# munia-snes.net
KiCad netlist of a schematic drawn in EAGLE
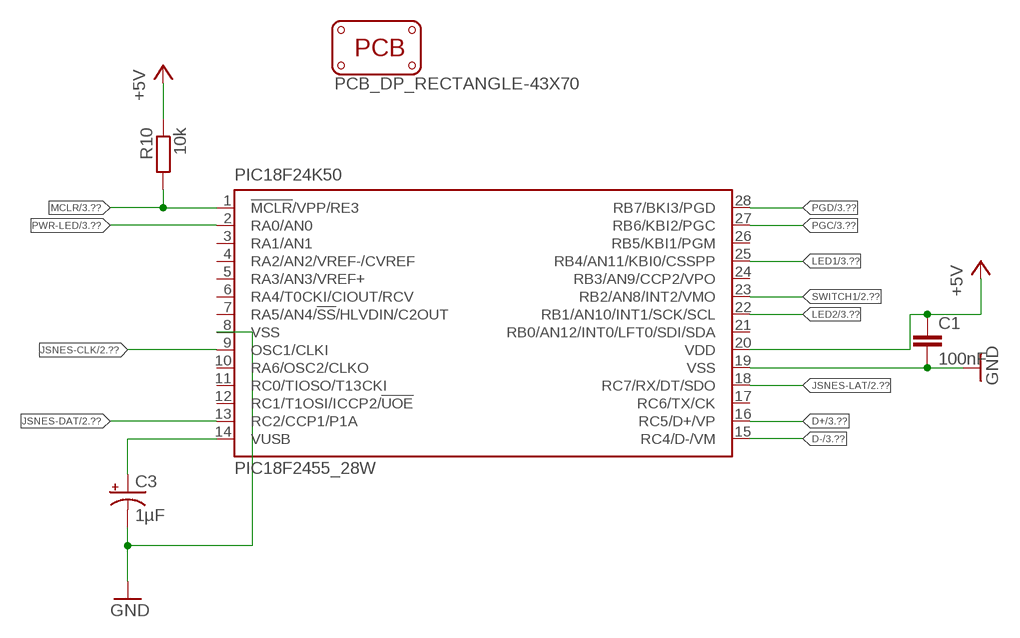
[diagram p0: schematic, sheet 1]
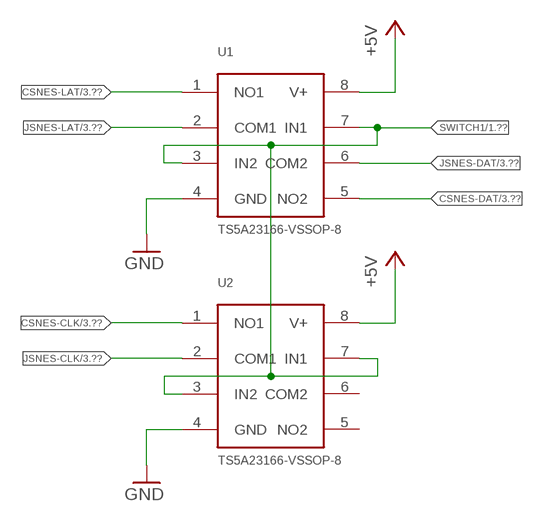
[diagram p1: schematic, sheet 2]
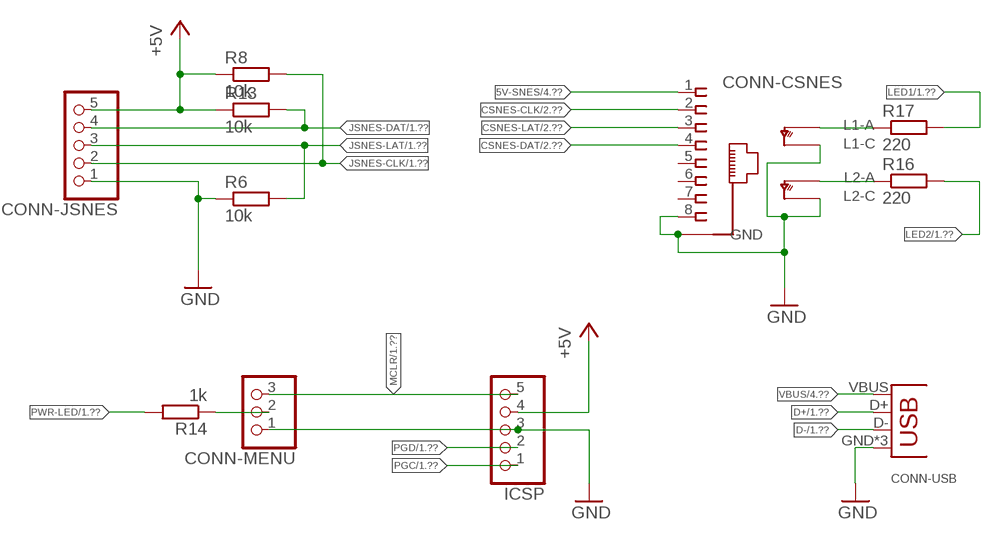
[diagram p2: schematic, sheet 3]
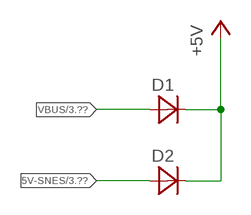
[diagram p3: schematic, sheet 4]

(export (version "E")
  (design (tool "Eeschema 10.0.6"))
  (components
    (comp (ref "C1")
      (value "100nF")
      (footprint "eagle-import:C0603")
      (libsource (lib "eagle-import") (part "C-EUC0603"))
    )
    (comp (ref "C3")
      (value "1µF")
      (footprint "eagle-import:EIA3216")
      (libsource (lib "eagle-import") (part "TANT-CAP1206"))
    )
    (comp (ref "PCB1")
      (value "PCB_DP_RECTANGLE-43X70")
      (footprint "eagle-import:DP7043_V1")
      (libsource (lib "eagle-import") (part "PCB_DP_RECTANGLE-43X70"))
    )
    (comp (ref "PIC18F24K50")
      (value "PIC18F2455_28W")
      (footprint "eagle-import:SO28W")
      (fields (field (name "MF") "MICROCHIP") (field (name "MPN") "PIC18F2455-I/SO"))
      (libsource (lib "eagle-import") (part "PIC18F2_28W455"))
    )
    (comp (ref "R10")
      (value "10k")
      (footprint "eagle-import:R0603")
      (libsource (lib "eagle-import") (part "R-EU_R0603"))
    )
    (comp (ref "U1")
      (value "TS5A23166-VSSOP-8")
      (footprint "eagle-import:SOT765")
      (libsource (lib "eagle-import") (part "TS5A23166-VSSOP-8"))
    )
    (comp (ref "U2")
      (value "TS5A23166-VSSOP-8")
      (footprint "eagle-import:SOT765")
      (libsource (lib "eagle-import") (part "TS5A23166-VSSOP-8"))
    )
    (comp (ref "CONN-CSNES")
      (value "RJ45-NIELS")
      (footprint "eagle-import:RJ45-NIELS")
      (libsource (lib "eagle-import") (part "RJ45-NIELS"))
    )
    (comp (ref "CONN-JSNES")
      (value "PINHD-1X5")
      (footprint "eagle-import:1X05")
      (libsource (lib "eagle-import") (part "PINHD-1X5"))
    )
    (comp (ref "CONN-MENU")
      (value "PINHD-1X3")
      (footprint "eagle-import:1X03")
      (libsource (lib "eagle-import") (part "PINHD-1X3"))
    )
    (comp (ref "CONN-USB")
      (value "USB-B-NIELS")
      (footprint "eagle-import:USB-B-H")
      (libsource (lib "eagle-import") (part "USB-B-NIELS"))
    )
    (comp (ref "ICSP")
      (value "PINHD-1X5")
      (footprint "eagle-import:1X05")
      (libsource (lib "eagle-import") (part "PINHD-1X5"))
    )
    (comp (ref "R6")
      (value "10k")
      (footprint "eagle-import:R0603")
      (libsource (lib "eagle-import") (part "R-EU_R0603"))
    )
    (comp (ref "R8")
      (value "10k")
      (footprint "eagle-import:R0603")
      (libsource (lib "eagle-import") (part "R-EU_R0603"))
    )
    (comp (ref "R13")
      (value "10k")
      (footprint "eagle-import:R0603")
      (libsource (lib "eagle-import") (part "R-EU_R0603"))
    )
    (comp (ref "R14")
      (value "1k")
      (footprint "eagle-import:R0603")
      (libsource (lib "eagle-import") (part "R-EU_R0603"))
    )
    (comp (ref "R16")
      (value "220")
      (footprint "eagle-import:R0603")
      (libsource (lib "eagle-import") (part "R-EU_R0603"))
    )
    (comp (ref "R17")
      (value "220")
      (footprint "eagle-import:R0603")
      (libsource (lib "eagle-import") (part "R-EU_R0603"))
    )
    (comp (ref "D1")
      (value "MBR120VLSFT1G")
      (footprint "eagle-import:SOD123")
      (libsource (lib "eagle-import") (part "MBR120VLSFT1G"))
    )
    (comp (ref "D2")
      (value "MBR120VLSFT1G")
      (footprint "eagle-import:SOD123")
      (libsource (lib "eagle-import") (part "MBR120VLSFT1G"))
    )
  )
  (nets
    (net (code "1") (name "+5V") (class "Default")
      (node (ref "C1") (pin "1") (pinfunction "1_1") (pintype "passive"))
      (node (ref "CONN-JSNES") (pin "5") (pinfunction "5_5") (pintype "passive"))
      (node (ref "D1") (pin "1") (pinfunction "C_1") (pintype "passive"))
      (node (ref "D2") (pin "1") (pinfunction "C_1") (pintype "passive"))
      (node (ref "ICSP") (pin "4") (pinfunction "4_4") (pintype "passive"))
      (node (ref "PIC18F24K50") (pin "20") (pinfunction "VDD_20") (pintype "power_in"))
      (node (ref "R10") (pin "1") (pinfunction "1_1") (pintype "passive"))
      (node (ref "R13") (pin "1") (pinfunction "1_1") (pintype "passive"))
      (node (ref "R8") (pin "1") (pinfunction "1_1") (pintype "passive"))
      (node (ref "U1") (pin "8") (pinfunction "V+_8") (pintype "bidirectional"))
      (node (ref "U2") (pin "8") (pinfunction "V+_8") (pintype "bidirectional"))
    )
    (net (code "2") (name "5V-SNES") (class "Default")
      (node (ref "CONN-CSNES") (pin "1") (pinfunction "1_1") (pintype "passive"))
      (node (ref "D2") (pin "2") (pinfunction "A_2") (pintype "passive"))
    )
    (net (code "3") (name "CSNES-CLK") (class "Default")
      (node (ref "CONN-CSNES") (pin "2") (pinfunction "2_2") (pintype "passive"))
      (node (ref "U2") (pin "1") (pinfunction "NO1_1") (pintype "bidirectional"))
    )
    (net (code "4") (name "CSNES-DAT") (class "Default")
      (node (ref "CONN-CSNES") (pin "4") (pinfunction "4_4") (pintype "passive"))
      (node (ref "U1") (pin "5") (pinfunction "NO2_5") (pintype "bidirectional"))
    )
    (net (code "5") (name "CSNES-LAT") (class "Default")
      (node (ref "CONN-CSNES") (pin "3") (pinfunction "3_3") (pintype "passive"))
      (node (ref "U1") (pin "1") (pinfunction "NO1_1") (pintype "bidirectional"))
    )
    (net (code "6") (name "D+") (class "Default")
      (node (ref "CONN-USB") (pin "D+") (pinfunction "D+_D+") (pintype "bidirectional"))
      (node (ref "PIC18F24K50") (pin "16") (pinfunction "RC5/D+/VP_16") (pintype "bidirectional"))
    )
    (net (code "7") (name "D-") (class "Default")
      (node (ref "CONN-USB") (pin "D-") (pinfunction "D-_D-") (pintype "bidirectional"))
      (node (ref "PIC18F24K50") (pin "15") (pinfunction "RC4/D-/VM_15") (pintype "bidirectional"))
    )
    (net (code "8") (name "GND") (class "Default")
      (node (ref "C1") (pin "2") (pinfunction "2_2") (pintype "passive"))
      (node (ref "C3") (pin "C") (pinfunction "-_C") (pintype "passive"))
      (node (ref "CONN-CSNES") (pin "8") (pinfunction "8_8") (pintype "passive"))
      (node (ref "CONN-CSNES") (pin "GND@5") (pinfunction "GND_GND@5") (pintype "power_in"))
      (node (ref "CONN-CSNES") (pin "GND@6") (pinfunction "GND_GND@6") (pintype "power_in"))
      (node (ref "CONN-CSNES") (pin "LED-GREEN-C") (pinfunction "L2C_LED-GREEN-C") (pintype "bidirectional"))
      (node (ref "CONN-CSNES") (pin "LED-ORANGE-C") (pinfunction "L1C_LED-ORANGE-C") (pintype "bidirectional"))
      (node (ref "CONN-JSNES") (pin "1") (pinfunction "1_1") (pintype "passive"))
      (node (ref "CONN-MENU") (pin "1") (pinfunction "1_1") (pintype "passive"))
      (node (ref "CONN-USB") (pin "GND") (pinfunction "GND_GND") (pintype "bidirectional"))
      (node (ref "CONN-USB") (pin "GND@1") (pinfunction "GND_GND@1") (pintype "bidirectional"))
      (node (ref "CONN-USB") (pin "GND@2") (pinfunction "GND_GND@2") (pintype "bidirectional"))
      (node (ref "ICSP") (pin "3") (pinfunction "3_3") (pintype "passive"))
      (node (ref "PIC18F24K50") (pin "19") (pinfunction "VSS_19") (pintype "power_in"))
      (node (ref "PIC18F24K50") (pin "8") (pinfunction "VSS_8") (pintype "power_in"))
      (node (ref "R6") (pin "1") (pinfunction "1_1") (pintype "passive"))
      (node (ref "U1") (pin "4") (pinfunction "GND_4") (pintype "bidirectional"))
      (node (ref "U2") (pin "4") (pinfunction "GND_4") (pintype "bidirectional"))
    )
    (net (code "9") (name "JSNES-CLK") (class "Default")
      (node (ref "CONN-JSNES") (pin "2") (pinfunction "2_2") (pintype "passive"))
      (node (ref "PIC18F24K50") (pin "9") (pinfunction "OSC1/CLKI_9") (pintype "input"))
      (node (ref "R8") (pin "2") (pinfunction "2_2") (pintype "passive"))
      (node (ref "U2") (pin "2") (pinfunction "COM1_2") (pintype "bidirectional"))
    )
    (net (code "10") (name "JSNES-DAT") (class "Default")
      (node (ref "CONN-JSNES") (pin "4") (pinfunction "4_4") (pintype "passive"))
      (node (ref "PIC18F24K50") (pin "13") (pinfunction "RC2/CCP1/P1A_13") (pintype "bidirectional"))
      (node (ref "R13") (pin "2") (pinfunction "2_2") (pintype "passive"))
      (node (ref "U1") (pin "6") (pinfunction "COM2_6") (pintype "bidirectional"))
    )
    (net (code "11") (name "JSNES-LAT") (class "Default")
      (node (ref "CONN-JSNES") (pin "3") (pinfunction "3_3") (pintype "passive"))
      (node (ref "PIC18F24K50") (pin "18") (pinfunction "RC7/RX/DT/SDO_18") (pintype "bidirectional"))
      (node (ref "R6") (pin "2") (pinfunction "2_2") (pintype "passive"))
      (node (ref "U1") (pin "2") (pinfunction "COM1_2") (pintype "bidirectional"))
    )
    (net (code "12") (name "LED1") (class "Default")
      (node (ref "PIC18F24K50") (pin "25") (pinfunction "RB4/AN11/KBI0/CSSPP_25") (pintype "bidirectional"))
      (node (ref "R17") (pin "2") (pinfunction "2_2") (pintype "passive"))
    )
    (net (code "13") (name "LED2") (class "Default")
      (node (ref "PIC18F24K50") (pin "22") (pinfunction "RB1/AN10/INT1/SCK/SCL_22") (pintype "bidirectional"))
      (node (ref "R16") (pin "2") (pinfunction "2_2") (pintype "passive"))
    )
    (net (code "14") (name "MCLR") (class "Default")
      (node (ref "CONN-MENU") (pin "3") (pinfunction "3_3") (pintype "passive"))
      (node (ref "ICSP") (pin "5") (pinfunction "5_5") (pintype "passive"))
      (node (ref "PIC18F24K50") (pin "1") (pinfunction "~{MCLR}/VPP/RE3_1") (pintype "input"))
      (node (ref "R10") (pin "2") (pinfunction "2_2") (pintype "passive"))
    )
    (net (code "15") (name "Net-(C3-+)") (class "Default")
      (node (ref "C3") (pin "A") (pinfunction "+_A") (pintype "passive"))
      (node (ref "PIC18F24K50") (pin "14") (pinfunction "VUSB_14") (pintype "bidirectional"))
    )
    (net (code "16") (name "Net-(CONN-CSNES-L1A)") (class "Default")
      (node (ref "CONN-CSNES") (pin "LED-ORANGE-A") (pinfunction "L1A_LED-ORANGE-A") (pintype "bidirectional"))
      (node (ref "R17") (pin "1") (pinfunction "1_1") (pintype "passive"))
    )
    (net (code "17") (name "Net-(CONN-CSNES-L2A)") (class "Default")
      (node (ref "CONN-CSNES") (pin "LED-GREEN-A") (pinfunction "L2A_LED-GREEN-A") (pintype "bidirectional"))
      (node (ref "R16") (pin "1") (pinfunction "1_1") (pintype "passive"))
    )
    (net (code "18") (name "Net-(CONN-MENU-Pad2)") (class "Default")
      (node (ref "CONN-MENU") (pin "2") (pinfunction "2_2") (pintype "passive"))
      (node (ref "R14") (pin "1") (pinfunction "1_1") (pintype "passive"))
    )
    (net (code "19") (name "PGC") (class "Default")
      (node (ref "ICSP") (pin "1") (pinfunction "1_1") (pintype "passive"))
      (node (ref "PIC18F24K50") (pin "27") (pinfunction "RB6/KBI2/PGC_27") (pintype "bidirectional"))
    )
    (net (code "20") (name "PGD") (class "Default")
      (node (ref "ICSP") (pin "2") (pinfunction "2_2") (pintype "passive"))
      (node (ref "PIC18F24K50") (pin "28") (pinfunction "RB7/BKI3/PGD_28") (pintype "bidirectional"))
    )
    (net (code "21") (name "PWR-LED") (class "Default")
      (node (ref "PIC18F24K50") (pin "2") (pinfunction "RA0/AN0_2") (pintype "bidirectional"))
      (node (ref "R14") (pin "2") (pinfunction "2_2") (pintype "passive"))
    )
    (net (code "22") (name "SWITCH1") (class "Default")
      (node (ref "PIC18F24K50") (pin "23") (pinfunction "RB2/AN8/INT2/VMO_23") (pintype "bidirectional"))
      (node (ref "U1") (pin "3") (pinfunction "IN2_3") (pintype "bidirectional"))
      (node (ref "U1") (pin "7") (pinfunction "IN1_7") (pintype "bidirectional"))
      (node (ref "U2") (pin "3") (pinfunction "IN2_3") (pintype "bidirectional"))
      (node (ref "U2") (pin "7") (pinfunction "IN1_7") (pintype "bidirectional"))
    )
    (net (code "23") (name "VBUS") (class "Default")
      (node (ref "CONN-USB") (pin "VBUS") (pinfunction "VBUS_VBUS") (pintype "bidirectional"))
      (node (ref "D1") (pin "2") (pinfunction "A_2") (pintype "passive"))
    )
    (net (code "24") (name "unconnected-(CONN-CSNES-Pad5)") (class "Default")
      (node (ref "CONN-CSNES") (pin "5") (pinfunction "5_5") (pintype "passive"))
    )
    (net (code "25") (name "unconnected-(CONN-CSNES-Pad6)") (class "Default")
      (node (ref "CONN-CSNES") (pin "6") (pinfunction "6_6") (pintype "passive"))
    )
    (net (code "26") (name "unconnected-(CONN-CSNES-Pad7)") (class "Default")
      (node (ref "CONN-CSNES") (pin "7") (pinfunction "7_7") (pintype "passive"))
    )
    (net (code "27") (name "unconnected-(PIC18F24K50-RA1{slash}AN1-Pad3)") (class "Default")
      (node (ref "PIC18F24K50") (pin "3") (pinfunction "RA1/AN1_3") (pintype "bidirectional"))
    )
    (net (code "28") (name "unconnected-(PIC18F24K50-RA2{slash}AN2{slash}VREF-{slash}CVREF-Pad4)") (class "Default")
      (node (ref "PIC18F24K50") (pin "4") (pinfunction "RA2/AN2/VREF-/CVREF_4") (pintype "bidirectional"))
    )
    (net (code "29") (name "unconnected-(PIC18F24K50-RA3{slash}AN3{slash}VREF+-Pad5)") (class "Default")
      (node (ref "PIC18F24K50") (pin "5") (pinfunction "RA3/AN3/VREF+_5") (pintype "bidirectional"))
    )
    (net (code "30") (name "unconnected-(PIC18F24K50-RA4{slash}T0CKI{slash}CIOUT{slash}RCV-Pad6)") (class "Default")
      (node (ref "PIC18F24K50") (pin "6") (pinfunction "RA4/T0CKI/CIOUT/RCV_6") (pintype "bidirectional"))
    )
    (net (code "31") (name "unconnected-(PIC18F24K50-RA5{slash}AN4{slash}~{SS}{slash}HLVDIN{slash}C2OUT-Pad7)") (class "Default")
      (node (ref "PIC18F24K50") (pin "7") (pinfunction "RA5/AN4/~{SS}/HLVDIN/C2OUT_7") (pintype "bidirectional"))
    )
    (net (code "32") (name "unconnected-(PIC18F24K50-RA6{slash}OSC2{slash}CLKO-Pad10)") (class "Default")
      (node (ref "PIC18F24K50") (pin "10") (pinfunction "RA6/OSC2/CLKO_10") (pintype "output"))
    )
    (net (code "33") (name "unconnected-(PIC18F24K50-RB0{slash}AN12{slash}INT0{slash}LFT0{slash}SDI{slash}SDA-Pad21)") (class "Default")
      (node (ref "PIC18F24K50") (pin "21") (pinfunction "RB0/AN12/INT0/LFT0/SDI/SDA_21") (pintype "bidirectional"))
    )
    (net (code "34") (name "unconnected-(PIC18F24K50-RB3{slash}AN9{slash}CCP2{slash}VPO-Pad24)") (class "Default")
      (node (ref "PIC18F24K50") (pin "24") (pinfunction "RB3/AN9/CCP2/VPO_24") (pintype "bidirectional"))
    )
    (net (code "35") (name "unconnected-(PIC18F24K50-RB5{slash}KBI1{slash}PGM-Pad26)") (class "Default")
      (node (ref "PIC18F24K50") (pin "26") (pinfunction "RB5/KBI1/PGM_26") (pintype "bidirectional"))
    )
    (net (code "36") (name "unconnected-(PIC18F24K50-RC0{slash}TIOSO{slash}T13CKI-Pad11)") (class "Default")
      (node (ref "PIC18F24K50") (pin "11") (pinfunction "RC0/TIOSO/T13CKI_11") (pintype "bidirectional"))
    )
    (net (code "37") (name "unconnected-(PIC18F24K50-RC1{slash}T1OSI{slash}ICCP2{slash}~{UOE}-Pad12)") (class "Default")
      (node (ref "PIC18F24K50") (pin "12") (pinfunction "RC1/T1OSI/ICCP2/~{UOE}_12") (pintype "bidirectional"))
    )
    (net (code "38") (name "unconnected-(PIC18F24K50-RC6{slash}TX{slash}CK-Pad17)") (class "Default")
      (node (ref "PIC18F24K50") (pin "17") (pinfunction "RC6/TX/CK_17") (pintype "bidirectional"))
    )
    (net (code "39") (name "unconnected-(U2-COM2-Pad6)") (class "Default")
      (node (ref "U2") (pin "6") (pinfunction "COM2_6") (pintype "bidirectional"))
    )
    (net (code "40") (name "unconnected-(U2-NO2-Pad5)") (class "Default")
      (node (ref "U2") (pin "5") (pinfunction "NO2_5") (pintype "bidirectional"))
    )
  )
)
